# adapter.net
KiCad netlist of a schematic drawn in EAGLE
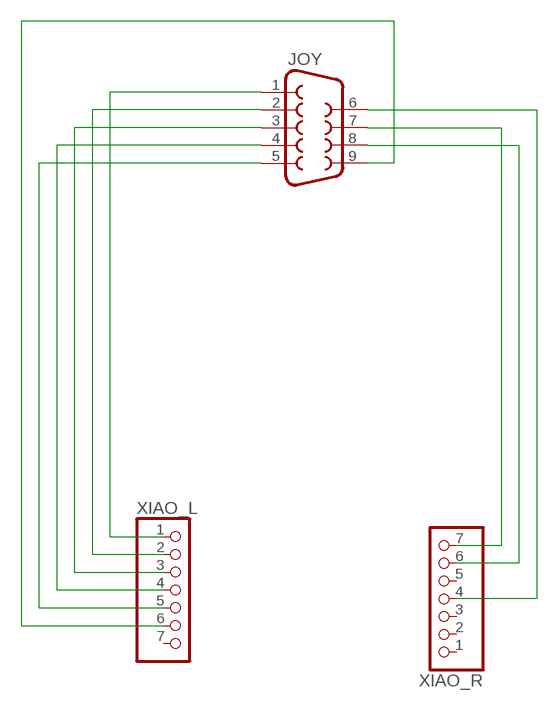
[diagram p0: schematic, sheet 1]

(export (version "E")
  (design (tool "Eeschema 10.0.6"))
  (components
    (comp (ref "JOY")
      (value "F09D")
      (footprint "eagle-import:F09D")
      (libsource (lib "eagle-import") (part "F09D"))
    )
    (comp (ref "XIAO_L")
      (value "PINHD-1X7")
      (footprint "eagle-import:1X07")
      (libsource (lib "eagle-import") (part "PINHD-1X7"))
    )
    (comp (ref "XIAO_R")
      (value "PINHD-1X7")
      (footprint "eagle-import:1X07")
      (libsource (lib "eagle-import") (part "PINHD-1X7"))
    )
  )
  (nets
    (net (code "1") (name "Net-(JOY-Pad1)") (class "Default")
      (node (ref "JOY") (pin "1") (pinfunction "1_1") (pintype "passive"))
      (node (ref "XIAO_L") (pin "1") (pinfunction "1_1") (pintype "passive"))
    )
    (net (code "2") (name "Net-(JOY-Pad2)") (class "Default")
      (node (ref "JOY") (pin "2") (pinfunction "2_2") (pintype "passive"))
      (node (ref "XIAO_L") (pin "2") (pinfunction "2_2") (pintype "passive"))
    )
    (net (code "3") (name "Net-(JOY-Pad3)") (class "Default")
      (node (ref "JOY") (pin "3") (pinfunction "3_3") (pintype "passive"))
      (node (ref "XIAO_L") (pin "3") (pinfunction "3_3") (pintype "passive"))
    )
    (net (code "4") (name "Net-(JOY-Pad4)") (class "Default")
      (node (ref "JOY") (pin "4") (pinfunction "4_4") (pintype "passive"))
      (node (ref "XIAO_L") (pin "4") (pinfunction "4_4") (pintype "passive"))
    )
    (net (code "5") (name "Net-(JOY-Pad5)") (class "Default")
      (node (ref "JOY") (pin "5") (pinfunction "5_5") (pintype "passive"))
      (node (ref "XIAO_L") (pin "5") (pinfunction "5_5") (pintype "passive"))
    )
    (net (code "6") (name "Net-(JOY-Pad6)") (class "Default")
      (node (ref "JOY") (pin "6") (pinfunction "6_6") (pintype "passive"))
      (node (ref "XIAO_R") (pin "4") (pinfunction "4_4") (pintype "passive"))
    )
    (net (code "7") (name "Net-(JOY-Pad7)") (class "Default")
      (node (ref "JOY") (pin "7") (pinfunction "7_7") (pintype "passive"))
      (node (ref "XIAO_R") (pin "7") (pinfunction "7_7") (pintype "passive"))
    )
    (net (code "8") (name "Net-(JOY-Pad8)") (class "Default")
      (node (ref "JOY") (pin "8") (pinfunction "8_8") (pintype "passive"))
      (node (ref "XIAO_R") (pin "6") (pinfunction "6_6") (pintype "passive"))
    )
    (net (code "9") (name "Net-(JOY-Pad9)") (class "Default")
      (node (ref "JOY") (pin "9") (pinfunction "9_9") (pintype "passive"))
      (node (ref "XIAO_L") (pin "6") (pinfunction "6_6") (pintype "passive"))
    )
    (net (code "10") (name "unconnected-(XIAO_L-Pad7)") (class "Default")
      (node (ref "XIAO_L") (pin "7") (pinfunction "7_7") (pintype "passive"))
    )
    (net (code "11") (name "unconnected-(XIAO_R-Pad1)") (class "Default")
      (node (ref "XIAO_R") (pin "1") (pinfunction "1_1") (pintype "passive"))
    )
    (net (code "12") (name "unconnected-(XIAO_R-Pad2)") (class "Default")
      (node (ref "XIAO_R") (pin "2") (pinfunction "2_2") (pintype "passive"))
    )
    (net (code "13") (name "unconnected-(XIAO_R-Pad3)") (class "Default")
      (node (ref "XIAO_R") (pin "3") (pinfunction "3_3") (pintype "passive"))
    )
    (net (code "14") (name "unconnected-(XIAO_R-Pad5)") (class "Default")
      (node (ref "XIAO_R") (pin "5") (pinfunction "5_5") (pintype "passive"))
    )
  )
)
